# circuit.net
KiCad netlist of a schematic drawn in EAGLE
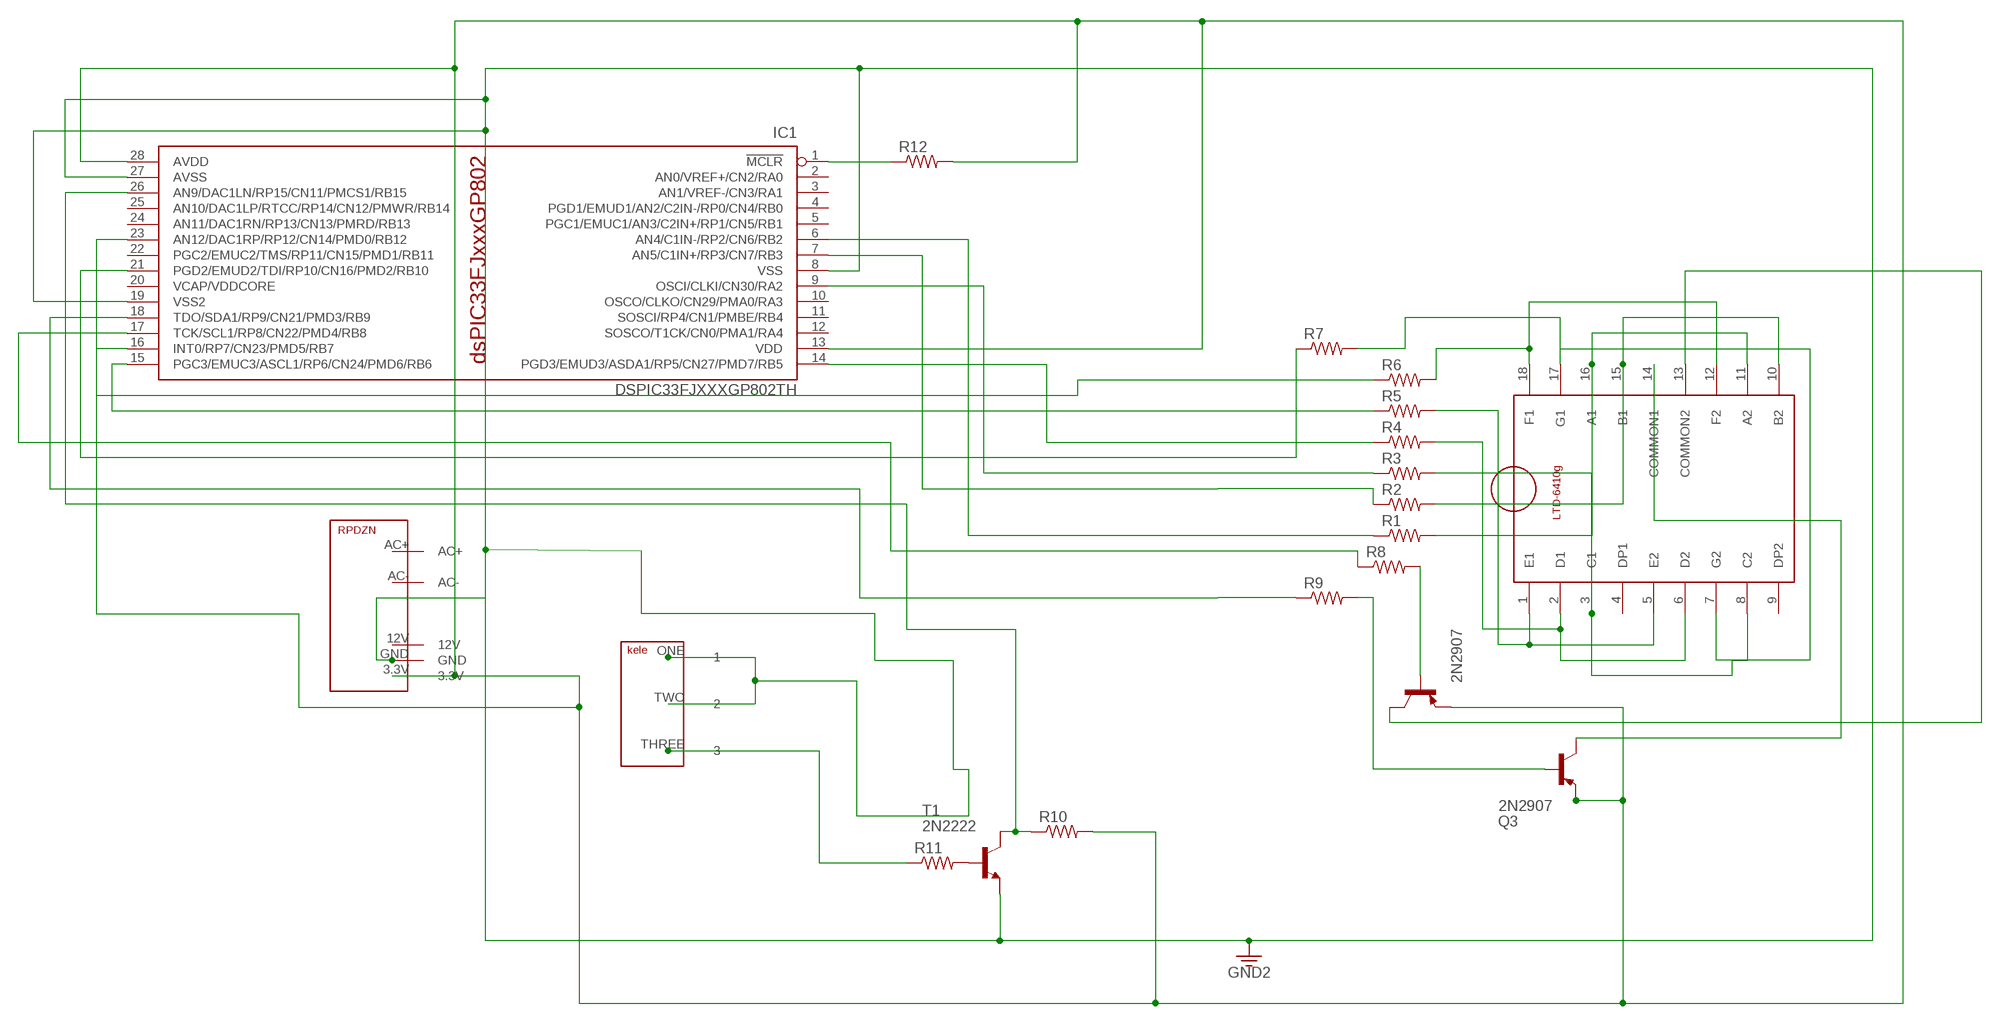
[diagram p0: schematic, sheet 1]

(export (version "E")
  (design (tool "Eeschema 10.0.6"))
  (components
    (comp (ref "IC1")
      (value "DSPIC33FJXXXGP802TH")
      (footprint "eagle-import:DIL28-3")
      (libsource (lib "eagle-import") (part "DSPIC33FJXXXGP802TH"))
    )
    (comp (ref "Q1")
      (value "2N2907")
      (footprint "eagle-import:TO92-EBC-OVAL")
      (libsource (lib "eagle-import") (part "2N2907"))
    )
    (comp (ref "Q3")
      (value "2N2907")
      (footprint "eagle-import:TO92-EBC-OVAL")
      (libsource (lib "eagle-import") (part "2N2907"))
    )
    (comp (ref "R1")
      (value "R-US_0207/9")
      (footprint "eagle-import:0207_9")
      (libsource (lib "eagle-import") (part "R-US_0207/9"))
    )
    (comp (ref "R2")
      (value "R-US_0207/9")
      (footprint "eagle-import:0207_9")
      (libsource (lib "eagle-import") (part "R-US_0207/9"))
    )
    (comp (ref "R3")
      (value "R-US_0207/9")
      (footprint "eagle-import:0207_9")
      (libsource (lib "eagle-import") (part "R-US_0207/9"))
    )
    (comp (ref "R4")
      (value "R-US_0207/9")
      (footprint "eagle-import:0207_9")
      (libsource (lib "eagle-import") (part "R-US_0207/9"))
    )
    (comp (ref "R5")
      (value "R-US_0207/9")
      (footprint "eagle-import:0207_9")
      (libsource (lib "eagle-import") (part "R-US_0207/9"))
    )
    (comp (ref "R6")
      (value "R-US_0207/9")
      (footprint "eagle-import:0207_9")
      (libsource (lib "eagle-import") (part "R-US_0207/9"))
    )
    (comp (ref "R7")
      (value "R-US_0207/9")
      (footprint "eagle-import:0207_9")
      (libsource (lib "eagle-import") (part "R-US_0207/9"))
    )
    (comp (ref "R8")
      (value "R-US_0207/9")
      (footprint "eagle-import:0207_9")
      (libsource (lib "eagle-import") (part "R-US_0207/9"))
    )
    (comp (ref "R9")
      (value "R-US_0207/9")
      (footprint "eagle-import:0207_9")
      (libsource (lib "eagle-import") (part "R-US_0207/9"))
    )
    (comp (ref "R10")
      (value "R-US_0207/9")
      (footprint "eagle-import:0207_9")
      (libsource (lib "eagle-import") (part "R-US_0207/9"))
    )
    (comp (ref "R11")
      (value "R-US_0207/9")
      (footprint "eagle-import:0207_9")
      (libsource (lib "eagle-import") (part "R-US_0207/9"))
    )
    (comp (ref "R12")
      (value "R-US_0207/9")
      (footprint "eagle-import:0207_9")
      (libsource (lib "eagle-import") (part "R-US_0207/9"))
    )
    (comp (ref "T1")
      (value "2N2222")
      (footprint "eagle-import:TO92-EBC-OVAL")
      (libsource (lib "eagle-import") (part "2N2222"))
    )
    (comp (ref "U$1")
      (value "TERMINALTHROUGH-HOLE")
      (footprint "eagle-import:TERMINAL")
      (libsource (lib "eagle-import") (part "TERMINALTHROUGH-HOLE"))
    )
    (comp (ref "U$2")
      (value "RODZN_AC-DC(3.3V)THROUGH-HOLE")
      (footprint "eagle-import:RODZN_AC-DC(3.3V)")
      (libsource (lib "eagle-import") (part "RODZN_AC-DC(3.3V)THROUGH-HOLE"))
    )
    (comp (ref "U$3")
      (value "LIB-2THROUGH_HOLE")
      (footprint "eagle-import:LIB-2")
      (libsource (lib "eagle-import") (part "LIB-2THROUGH_HOLE"))
    )
  )
  (nets
    (net (code "1") (name "/VCAP{slash}VDDCORE") (class "Default")
      (node (ref "IC1") (pin "20") (pinfunction "VCAP/VDDCORE_20") (pintype "power_in"))
    )
    (net (code "2") (name "GND2") (class "Default")
      (node (ref "IC1") (pin "19") (pinfunction "VSS2_19") (pintype "power_in"))
      (node (ref "IC1") (pin "27") (pinfunction "AVSS_27") (pintype "power_in"))
      (node (ref "IC1") (pin "8") (pinfunction "VSS_8") (pintype "power_in"))
      (node (ref "T1") (pin "E") (pinfunction "E_E") (pintype "passive"))
      (node (ref "U$1") (pin "ONE") (pinfunction "1_ONE") (pintype "bidirectional"))
      (node (ref "U$1") (pin "TWO") (pinfunction "2_TWO") (pintype "bidirectional"))
      (node (ref "U$2") (pin "GND") (pinfunction "GND_GND") (pintype "bidirectional"))
    )
    (net (code "3") (name "Net-(IC1-AN4{slash}C1IN-{slash}RP2{slash}CN6{slash}RB2)") (class "Default")
      (node (ref "IC1") (pin "6") (pinfunction "AN4/C1IN-/RP2/CN6/RB2_6") (pintype "bidirectional"))
      (node (ref "R1") (pin "1") (pinfunction "1_1") (pintype "passive"))
    )
    (net (code "4") (name "Net-(IC1-AN5{slash}C1IN+{slash}RP3{slash}CN7{slash}RB3)") (class "Default")
      (node (ref "IC1") (pin "7") (pinfunction "AN5/C1IN+/RP3/CN7/RB3_7") (pintype "bidirectional"))
      (node (ref "R2") (pin "1") (pinfunction "1_1") (pintype "passive"))
    )
    (net (code "5") (name "Net-(IC1-AN9{slash}DAC1LN{slash}RP15{slash}CN11{slash}PMCS1{slash}RB15)") (class "Default")
      (node (ref "IC1") (pin "26") (pinfunction "AN9/DAC1LN/RP15/CN11/PMCS1/RB15_26") (pintype "bidirectional"))
      (node (ref "R10") (pin "1") (pinfunction "1_1") (pintype "passive"))
      (node (ref "T1") (pin "C") (pinfunction "C_C") (pintype "passive"))
    )
    (net (code "6") (name "Net-(IC1-AN12{slash}DAC1RP{slash}RP12{slash}CN14{slash}PMD0{slash}RB12)") (class "Default")
      (node (ref "IC1") (pin "13") (pinfunction "VDD_13") (pintype "power_in"))
      (node (ref "IC1") (pin "23") (pinfunction "AN12/DAC1RP/RP12/CN14/PMD0/RB12_23") (pintype "bidirectional"))
      (node (ref "IC1") (pin "28") (pinfunction "AVDD_28") (pintype "power_in"))
      (node (ref "Q1") (pin "E") (pinfunction "E_E") (pintype "passive"))
      (node (ref "Q3") (pin "E") (pinfunction "E_E") (pintype "passive"))
      (node (ref "R10") (pin "2") (pinfunction "2_2") (pintype "passive"))
      (node (ref "R12") (pin "2") (pinfunction "2_2") (pintype "passive"))
      (node (ref "U$2") (pin "3.3V") (pinfunction "3.3V_3.3V") (pintype "bidirectional"))
    )
    (net (code "7") (name "Net-(IC1-INT0{slash}RP7{slash}CN23{slash}PMD5{slash}RB7)") (class "Default")
      (node (ref "IC1") (pin "16") (pinfunction "INT0/RP7/CN23/PMD5/RB7_16") (pintype "bidirectional"))
      (node (ref "R6") (pin "1") (pinfunction "1_1") (pintype "passive"))
    )
    (net (code "8") (name "Net-(IC1-OSCI{slash}CLKI{slash}CN30{slash}RA2)") (class "Default")
      (node (ref "IC1") (pin "9") (pinfunction "OSCI/CLKI/CN30/RA2_9") (pintype "bidirectional"))
      (node (ref "R3") (pin "1") (pinfunction "1_1") (pintype "passive"))
    )
    (net (code "9") (name "Net-(IC1-PGC3{slash}EMUC3{slash}ASCL1{slash}RP6{slash}CN24{slash}PMD6{slash}RB6)") (class "Default")
      (node (ref "IC1") (pin "15") (pinfunction "PGC3/EMUC3/ASCL1/RP6/CN24/PMD6/RB6_15") (pintype "bidirectional"))
      (node (ref "R5") (pin "1") (pinfunction "1_1") (pintype "passive"))
    )
    (net (code "10") (name "Net-(IC1-PGD2{slash}EMUD2{slash}TDI{slash}RP10{slash}CN16{slash}PMD2{slash}RB10)") (class "Default")
      (node (ref "IC1") (pin "21") (pinfunction "PGD2/EMUD2/TDI/RP10/CN16/PMD2/RB10_21") (pintype "bidirectional"))
      (node (ref "R7") (pin "1") (pinfunction "1_1") (pintype "passive"))
    )
    (net (code "11") (name "Net-(IC1-PGD3{slash}EMUD3{slash}ASDA1{slash}RP5{slash}CN27{slash}PMD7{slash}RB5)") (class "Default")
      (node (ref "IC1") (pin "14") (pinfunction "PGD3/EMUD3/ASDA1/RP5/CN27/PMD7/RB5_14") (pintype "bidirectional"))
      (node (ref "R4") (pin "1") (pinfunction "1_1") (pintype "passive"))
    )
    (net (code "12") (name "Net-(IC1-TCK{slash}SCL1{slash}RP8{slash}CN22{slash}PMD4{slash}RB8)") (class "Default")
      (node (ref "IC1") (pin "17") (pinfunction "TCK/SCL1/RP8/CN22/PMD4/RB8_17") (pintype "bidirectional"))
      (node (ref "R8") (pin "1") (pinfunction "1_1") (pintype "passive"))
    )
    (net (code "13") (name "Net-(IC1-TDO{slash}SDA1{slash}RP9{slash}CN21{slash}PMD3{slash}RB9)") (class "Default")
      (node (ref "IC1") (pin "18") (pinfunction "TDO/SDA1/RP9/CN21/PMD3/RB9_18") (pintype "bidirectional"))
      (node (ref "R9") (pin "1") (pinfunction "1_1") (pintype "passive"))
    )
    (net (code "14") (name "Net-(IC1-~{MCLR})") (class "Default")
      (node (ref "IC1") (pin "1") (pinfunction "~{MCLR}_1") (pintype "input"))
      (node (ref "R12") (pin "1") (pinfunction "1_1") (pintype "passive"))
    )
    (net (code "15") (name "Net-(Q1-PadB)") (class "Default")
      (node (ref "Q1") (pin "B") (pinfunction "B_B") (pintype "passive"))
      (node (ref "R8") (pin "2") (pinfunction "2_2") (pintype "passive"))
    )
    (net (code "16") (name "Net-(Q3-PadB)") (class "Default")
      (node (ref "Q3") (pin "B") (pinfunction "B_B") (pintype "passive"))
      (node (ref "R9") (pin "2") (pinfunction "2_2") (pintype "passive"))
    )
    (net (code "17") (name "Net-(R11-Pad2)") (class "Default")
      (node (ref "R11") (pin "2") (pinfunction "2_2") (pintype "passive"))
      (node (ref "T1") (pin "B") (pinfunction "B_B") (pintype "passive"))
    )
    (net (code "18") (name "Net-(U$1-3)") (class "Default")
      (node (ref "R11") (pin "1") (pinfunction "1_1") (pintype "passive"))
      (node (ref "U$1") (pin "THREE") (pinfunction "3_THREE") (pintype "bidirectional"))
    )
    (net (code "19") (name "Net-(U$3-A1)") (class "Default")
      (node (ref "R1") (pin "2") (pinfunction "2_2") (pintype "passive"))
      (node (ref "U$3") (pin "11") (pinfunction "A2_11") (pintype "bidirectional"))
      (node (ref "U$3") (pin "16") (pinfunction "A1_16") (pintype "bidirectional"))
    )
    (net (code "20") (name "Net-(U$3-B1)") (class "Default")
      (node (ref "R2") (pin "2") (pinfunction "2_2") (pintype "passive"))
      (node (ref "U$3") (pin "10") (pinfunction "B2_10") (pintype "bidirectional"))
      (node (ref "U$3") (pin "15") (pinfunction "B1_15") (pintype "bidirectional"))
    )
    (net (code "21") (name "Net-(U$3-C1)") (class "Default")
      (node (ref "R3") (pin "2") (pinfunction "2_2") (pintype "passive"))
      (node (ref "U$3") (pin "3") (pinfunction "C1_3") (pintype "bidirectional"))
      (node (ref "U$3") (pin "8") (pinfunction "C2_8") (pintype "bidirectional"))
    )
    (net (code "22") (name "Net-(U$3-COMMON1)") (class "Default")
      (node (ref "Q3") (pin "C") (pinfunction "C_C") (pintype "passive"))
      (node (ref "U$3") (pin "14") (pinfunction "COMMON1_14") (pintype "bidirectional"))
    )
    (net (code "23") (name "Net-(U$3-COMMON2)") (class "Default")
      (node (ref "Q1") (pin "C") (pinfunction "C_C") (pintype "passive"))
      (node (ref "U$3") (pin "13") (pinfunction "COMMON2_13") (pintype "bidirectional"))
    )
    (net (code "24") (name "Net-(U$3-D1)") (class "Default")
      (node (ref "R4") (pin "2") (pinfunction "2_2") (pintype "passive"))
      (node (ref "U$3") (pin "2") (pinfunction "D1_2") (pintype "bidirectional"))
      (node (ref "U$3") (pin "6") (pinfunction "D2_6") (pintype "bidirectional"))
    )
    (net (code "25") (name "Net-(U$3-E1)") (class "Default")
      (node (ref "R5") (pin "2") (pinfunction "2_2") (pintype "passive"))
      (node (ref "U$3") (pin "1") (pinfunction "E1_1") (pintype "bidirectional"))
      (node (ref "U$3") (pin "5") (pinfunction "E2_5") (pintype "bidirectional"))
    )
    (net (code "26") (name "Net-(U$3-F1)") (class "Default")
      (node (ref "R6") (pin "2") (pinfunction "2_2") (pintype "passive"))
      (node (ref "U$3") (pin "12") (pinfunction "F2_12") (pintype "bidirectional"))
      (node (ref "U$3") (pin "18") (pinfunction "F1_18") (pintype "bidirectional"))
    )
    (net (code "27") (name "Net-(U$3-G1)") (class "Default")
      (node (ref "R7") (pin "2") (pinfunction "2_2") (pintype "passive"))
      (node (ref "U$3") (pin "17") (pinfunction "G1_17") (pintype "bidirectional"))
      (node (ref "U$3") (pin "7") (pinfunction "G2_7") (pintype "bidirectional"))
    )
    (net (code "28") (name "unconnected-(IC1-AN0{slash}VREF+{slash}CN2{slash}RA0-Pad2)") (class "Default")
      (node (ref "IC1") (pin "2") (pinfunction "AN0/VREF+/CN2/RA0_2") (pintype "bidirectional"))
    )
    (net (code "29") (name "unconnected-(IC1-AN1{slash}VREF-{slash}CN3{slash}RA1-Pad3)") (class "Default")
      (node (ref "IC1") (pin "3") (pinfunction "AN1/VREF-/CN3/RA1_3") (pintype "bidirectional"))
    )
    (net (code "30") (name "unconnected-(IC1-AN10{slash}DAC1LP{slash}RTCC{slash}RP14{slash}CN12{slash}PMWR{slash}RB14-Pad25)") (class "Default")
      (node (ref "IC1") (pin "25") (pinfunction "AN10/DAC1LP/RTCC/RP14/CN12/PMWR/RB14_25") (pintype "bidirectional"))
    )
    (net (code "31") (name "unconnected-(IC1-AN11{slash}DAC1RN{slash}RP13{slash}CN13{slash}PMRD{slash}RB13-Pad24)") (class "Default")
      (node (ref "IC1") (pin "24") (pinfunction "AN11/DAC1RN/RP13/CN13/PMRD/RB13_24") (pintype "bidirectional"))
    )
    (net (code "32") (name "unconnected-(IC1-OSCO{slash}CLKO{slash}CN29{slash}PMA0{slash}RA3-Pad10)") (class "Default")
      (node (ref "IC1") (pin "10") (pinfunction "OSCO/CLKO/CN29/PMA0/RA3_10") (pintype "bidirectional"))
    )
    (net (code "33") (name "unconnected-(IC1-PGC1{slash}EMUC1{slash}AN3{slash}C2IN+{slash}RP1{slash}CN5{slash}RB1-Pad5)") (class "Default")
      (node (ref "IC1") (pin "5") (pinfunction "PGC1/EMUC1/AN3/C2IN+/RP1/CN5/RB1_5") (pintype "bidirectional"))
    )
    (net (code "34") (name "unconnected-(IC1-PGC2{slash}EMUC2{slash}TMS{slash}RP11{slash}CN15{slash}PMD1{slash}RB11-Pad22)") (class "Default")
      (node (ref "IC1") (pin "22") (pinfunction "PGC2/EMUC2/TMS/RP11/CN15/PMD1/RB11_22") (pintype "bidirectional"))
    )
    (net (code "35") (name "unconnected-(IC1-PGD1{slash}EMUD1{slash}AN2{slash}C2IN-{slash}RP0{slash}CN4{slash}RB0-Pad4)") (class "Default")
      (node (ref "IC1") (pin "4") (pinfunction "PGD1/EMUD1/AN2/C2IN-/RP0/CN4/RB0_4") (pintype "bidirectional"))
    )
    (net (code "36") (name "unconnected-(IC1-SOSCI{slash}RP4{slash}CN1{slash}PMBE{slash}RB4-Pad11)") (class "Default")
      (node (ref "IC1") (pin "11") (pinfunction "SOSCI/RP4/CN1/PMBE/RB4_11") (pintype "bidirectional"))
    )
    (net (code "37") (name "unconnected-(IC1-SOSCO{slash}T1CK{slash}CN0{slash}PMA1{slash}RA4-Pad12)") (class "Default")
      (node (ref "IC1") (pin "12") (pinfunction "SOSCO/T1CK/CN0/PMA1/RA4_12") (pintype "bidirectional"))
    )
    (net (code "38") (name "unconnected-(U$2-Pad12V)") (class "Default")
      (node (ref "U$2") (pin "12V") (pinfunction "12V_12V") (pintype "bidirectional"))
    )
    (net (code "39") (name "unconnected-(U$2-PadAC+)") (class "Default")
      (node (ref "U$2") (pin "AC+") (pinfunction "AC+_AC+") (pintype "bidirectional"))
    )
    (net (code "40") (name "unconnected-(U$2-PadAC-)") (class "Default")
      (node (ref "U$2") (pin "AC-") (pinfunction "AC-_AC-") (pintype "bidirectional"))
    )
    (net (code "41") (name "unconnected-(U$3-DP1-Pad4)") (class "Default")
      (node (ref "U$3") (pin "4") (pinfunction "DP1_4") (pintype "bidirectional"))
    )
    (net (code "42") (name "unconnected-(U$3-DP2-Pad9)") (class "Default")
      (node (ref "U$3") (pin "9") (pinfunction "DP2_9") (pintype "bidirectional"))
    )
  )
)
